# radio.net
KiCad netlist of a schematic drawn in Altium Designer
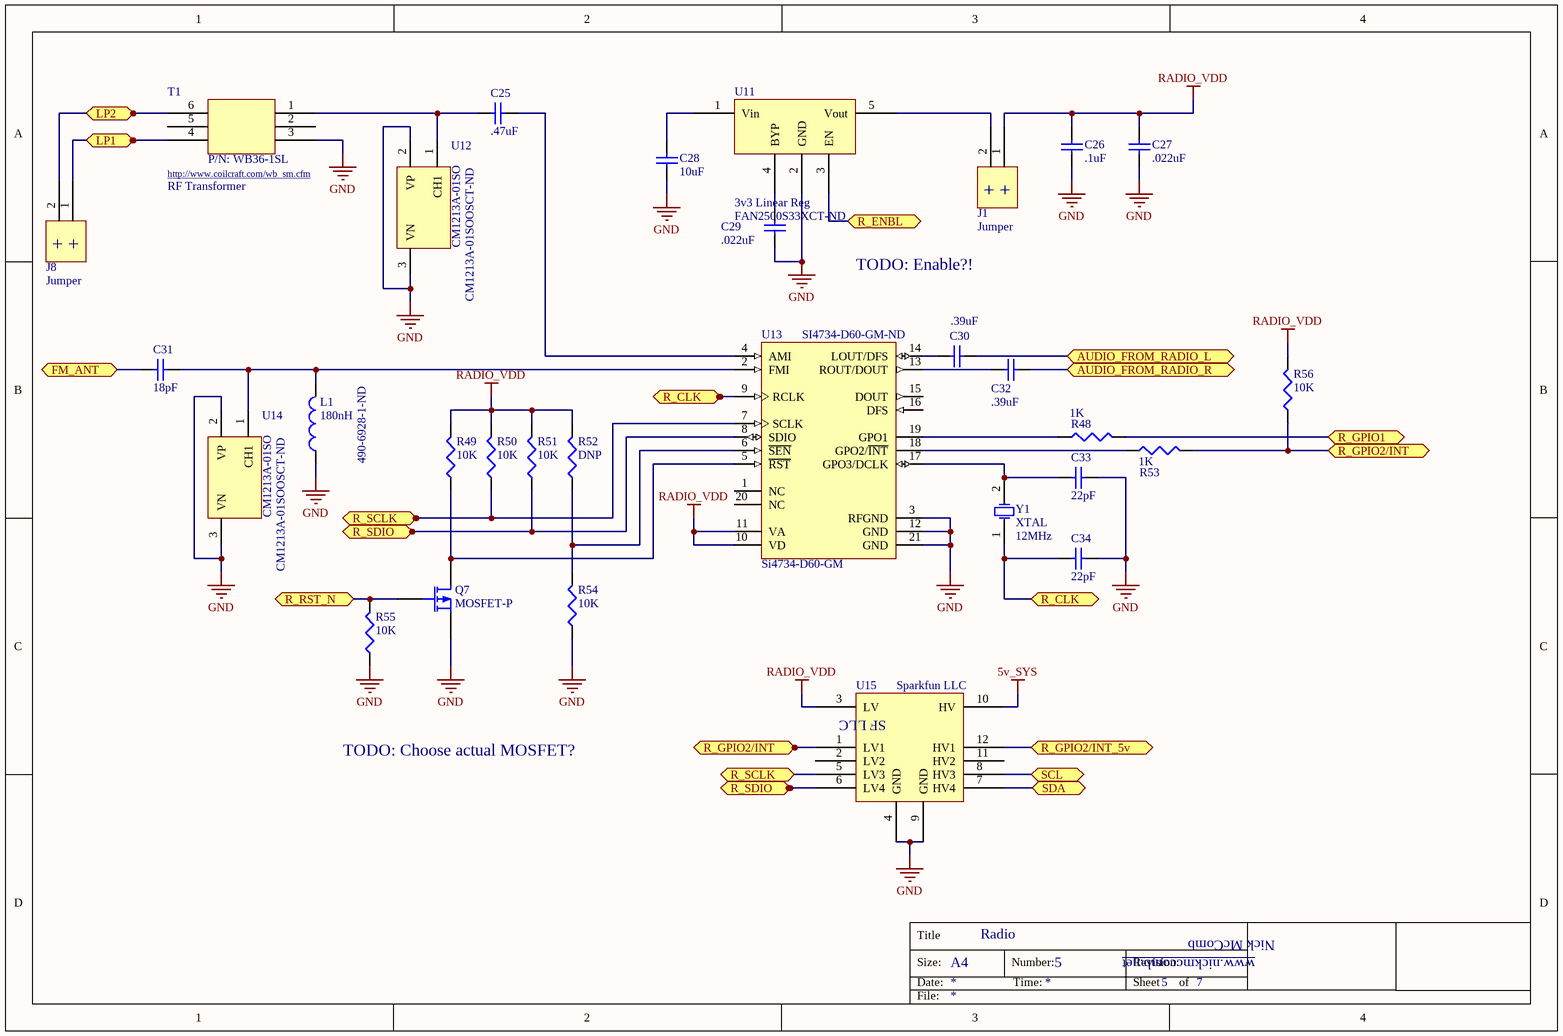
[diagram p0: radio.SchDoc]

(export (version "E")
  (design (tool "Eeschema 10.0.6"))
  (components
    (comp (ref "C25")
      (value ".47uF")
      (footprint "C0805")
      (description "Capacitor")
      (fields (field (name "Comment") "0805 style, by default") (field (name "PUBLISHER") "Altium Limited"))
      (libsource (lib "lab2") (part "Cap"))
    )
    (comp (ref "C26")
      (value ".1uF")
      (footprint "C0805")
      (description "Capacitor")
      (fields (field (name "Comment") "0805 style, by default") (field (name "PUBLISHER") "Altium Limited"))
      (libsource (lib "lab2") (part "Cap"))
    )
    (comp (ref "C27")
      (value ".022uF")
      (footprint "C0805")
      (description "Capacitor")
      (fields (field (name "Comment") "0805 style, by default") (field (name "PUBLISHER") "Altium Limited"))
      (libsource (lib "lab2") (part "Cap"))
    )
    (comp (ref "C28")
      (value "10uF")
      (footprint "C0805")
      (description "Capacitor")
      (fields (field (name "Comment") "0805 style, by default") (field (name "PUBLISHER") "Altium Limited"))
      (libsource (lib "lab2") (part "Cap"))
    )
    (comp (ref "C29")
      (value ".022uF")
      (footprint "C0805")
      (description "Capacitor")
      (fields (field (name "Comment") "0805 style, by default") (field (name "PUBLISHER") "Altium Limited"))
      (libsource (lib "lab2") (part "Cap"))
    )
    (comp (ref "C30")
      (value ".39uF")
      (footprint "C0805")
      (description "Capacitor")
      (fields (field (name "Comment") "0805 style, by default") (field (name "PUBLISHER") "Altium Limited"))
      (libsource (lib "lab2") (part "Cap"))
    )
    (comp (ref "C31")
      (value "18pF")
      (footprint "C0805")
      (description "Capacitor")
      (fields (field (name "Comment") "0805 style, by default") (field (name "PUBLISHER") "Altium Limited"))
      (libsource (lib "lab2") (part "Cap"))
    )
    (comp (ref "C32")
      (value ".39uF")
      (footprint "C0805")
      (description "Capacitor")
      (fields (field (name "Comment") "0805 style, by default") (field (name "PUBLISHER") "Altium Limited"))
      (libsource (lib "lab2") (part "Cap"))
    )
    (comp (ref "C33")
      (value "22pF")
      (footprint "C0805")
      (description "Capacitor")
      (fields (field (name "Comment") "0805 style, by default") (field (name "PUBLISHER") "Altium Limited"))
      (libsource (lib "lab2") (part "Cap"))
    )
    (comp (ref "C34")
      (value "22pF")
      (footprint "C0805")
      (description "Capacitor")
      (fields (field (name "Comment") "0805 style, by default") (field (name "PUBLISHER") "Altium Limited"))
      (libsource (lib "lab2") (part "Cap"))
    )
    (comp (ref "J1") (value "Jumper") (footprint "Jumper") (libsource (lib "lab2") (part "Jumper")))
    (comp (ref "J8") (value "Jumper") (footprint "Jumper") (libsource (lib "lab2") (part "Jumper")))
    (comp (ref "L1")
      (value "180nH")
      (footprint "J1-0603")
      (description "Inductor")
      (fields
        (field (name "SUPPLIER PART NUMBER 1") "490-6928-1-ND")
        (field (name "MANUFACTURER") "Murata")
        (field (name "MANUFACTURER PART NUMBER") "LQW18ANR18J00D")
      )
      (libsource (lib "lab2") (part "Inductor"))
    )
    (comp (ref "Q7")
      (value "MOSFET-P")
      (footprint "E3")
      (description "P-Channel MOSFET")
      (fields (field (name "PUBLISHER") "Altium Limited"))
      (libsource (lib "Miscellaneous Devices") (part "MOSFET-P"))
    )
    (comp (ref "R48")
      (value "1K")
      (footprint "J1-0603")
      (description "Resistor")
      (fields (field (name "PUBLISHER") "Altium Limited"))
      (libsource (lib "lab2") (part "Res3"))
    )
    (comp (ref "R49")
      (value "10K")
      (footprint "J1-0603")
      (description "Resistor")
      (fields (field (name "PUBLISHER") "Altium Limited"))
      (libsource (lib "lab2") (part "Res3"))
    )
    (comp (ref "R50")
      (value "10K")
      (footprint "J1-0603")
      (description "Resistor")
      (fields (field (name "PUBLISHER") "Altium Limited"))
      (libsource (lib "lab2") (part "Res3"))
    )
    (comp (ref "R51")
      (value "10K")
      (footprint "J1-0603")
      (description "Resistor")
      (fields (field (name "PUBLISHER") "Altium Limited"))
      (libsource (lib "lab2") (part "Res3"))
    )
    (comp (ref "R52")
      (value "DNP")
      (footprint "J1-0603")
      (description "Resistor")
      (fields (field (name "PUBLISHER") "Altium Limited"))
      (libsource (lib "lab2") (part "Res3"))
    )
    (comp (ref "R53")
      (value "1K")
      (footprint "J1-0603")
      (description "Resistor")
      (fields (field (name "PUBLISHER") "Altium Limited"))
      (libsource (lib "lab2") (part "Res3"))
    )
    (comp (ref "R54")
      (value "10K")
      (footprint "J1-0603")
      (description "Resistor")
      (fields (field (name "PUBLISHER") "Altium Limited"))
      (libsource (lib "lab2") (part "Res3"))
    )
    (comp (ref "R55")
      (value "10K")
      (footprint "J1-0603")
      (description "Resistor")
      (fields (field (name "PUBLISHER") "Altium Limited"))
      (libsource (lib "lab2") (part "Res3"))
    )
    (comp (ref "R56")
      (value "10K")
      (footprint "J1-0603")
      (description "Resistor")
      (fields (field (name "PUBLISHER") "Altium Limited"))
      (libsource (lib "lab2") (part "Res3"))
    )
    (comp (ref "T1")
      (value "RF Transformer")
      (footprint "WB Series RF Transformers")
      (libsource (lib "lab2") (part "RF Transformer"))
    )
    (comp (ref "U11")
      (value "3v3 Linear Reg")
      (footprint "SOT95P245X110-5N")
      (fields
        (field (name "MANUFACTURER") "Fairchild Semiconductor")
        (field (name "MANUFACTURER PART NUMBER") "FAN2500S33X")
        (field (name "SUPPLIER PART NUMBER 1") "FAN2500S33XCT-ND")
      )
      (libsource (lib "lab2") (part "3v3 Linear Reg"))
    )
    (comp (ref "U12")
      (value "CM1213A-01SO")
      (footprint "ONSC-SOT-23-3-318-08_V")
      (description "1-Channel Low Capacitance ESD Protection Array, 3-Pin SOT-23, Pb-Free, Tape and Reel")
      (fields
        (field (name "MANUFACTURER") "On Semiconductor")
        (field (name "SUPPLIER PART NUMBER 1") "CM1213A-01SOOSCT-ND")
      )
      (libsource (lib "Altium Content Vault") (part "ONSC-CM1213A-SOT-23-3-318-08"))
    )
    (comp (ref "U13")
      (value "Si4734-D60-GM")
      (footprint "SLAB-QFN-20-1700x1700TP_V")
      (description "Broadcast AM / FM / SW / LW Radio Receiver, -20 to 85 degC, 20-pin QFN, Tray")
      (fields
        (field (name "MANUFACTURER") "Silicon Labs")
        (field (name "SUPPLIER PART NUMBER 1") "SI4734-D60-GM-ND")
        (field (name "MANUFACTURER PART NUMBER") "SI4734-D60-GM")
      )
      (libsource (lib "Altium Content Vault") (part "SLAB-Si473X-QFN-20-21"))
    )
    (comp (ref "U14")
      (value "CM1213A-01SO")
      (footprint "ONSC-SOT-23-3-318-08_V")
      (description "1-Channel Low Capacitance ESD Protection Array, 3-Pin SOT-23, Pb-Free, Tape and Reel")
      (fields
        (field (name "MANUFACTURER") "On Semiconductor")
        (field (name "SUPPLIER PART NUMBER 1") "CM1213A-01SOOSCT-ND")
      )
      (libsource (lib "Altium Content Vault") (part "ONSC-CM1213A-SOT-23-3-318-08"))
    )
    (comp (ref "U15")
      (value "Sparkfun LLC")
      (footprint "Sparkfun LLC")
      (libsource (lib "ROSS_PDB") (part "Sparkfun LLC"))
    )
    (comp (ref "Y1")
      (value "XTAL")
      (footprint "XTAL_PDB")
      (description "Crystal Oscillator")
      (fields (field (name "FREQUENCY") "12MHz"))
      (libsource (lib "lab2") (part "XTAL GENERIC"))
    )
  )
  (nets
    (net (code "1") (name "/AUDIO_FROM_RADIO_L") (class "Default")
      (node (ref "C30") (pin "2") (pinfunction "2_2") (pintype "passive"))
    )
    (net (code "2") (name "/AUDIO_FROM_RADIO_R") (class "Default")
      (node (ref "C32") (pin "2") (pinfunction "2_2") (pintype "passive"))
    )
    (net (code "3") (name "/FM_ANT") (class "Default")
      (node (ref "C31") (pin "2") (pinfunction "2_2") (pintype "passive"))
    )
    (net (code "4") (name "/LP1") (class "Default")
      (node (ref "J8") (pin "1") (pintype "passive"))
      (node (ref "T1") (pin "4") (pintype "passive"))
    )
    (net (code "5") (name "/LP2") (class "Default")
      (node (ref "J8") (pin "2") (pintype "passive"))
      (node (ref "T1") (pin "6") (pintype "passive"))
    )
    (net (code "6") (name "/R_CLK") (class "Default")
      (node (ref "C34") (pin "2") (pinfunction "2_2") (pintype "passive"))
      (node (ref "U13") (pin "9") (pinfunction "RCLK_9") (pintype "input"))
      (node (ref "Y1") (pin "1") (pinfunction "OSC1_1") (pintype "passive"))
    )
    (net (code "7") (name "/R_ENBL") (class "Default")
      (node (ref "U11") (pin "3") (pinfunction "EN_3") (pintype "passive"))
    )
    (net (code "8") (name "/R_GPIO1") (class "Default")
      (node (ref "R48") (pin "2") (pinfunction "2_2") (pintype "passive"))
    )
    (net (code "9") (name "/R_GPIO2{slash}INT") (class "Default")
      (node (ref "R53") (pin "2") (pinfunction "2_2") (pintype "passive"))
      (node (ref "R56") (pin "1") (pinfunction "1_1") (pintype "passive"))
      (node (ref "U15") (pin "1") (pinfunction "LV1_1") (pintype "passive"))
    )
    (net (code "10") (name "/R_GPIO2{slash}INT_5v") (class "Default")
      (node (ref "U15") (pin "12") (pinfunction "HV1_12") (pintype "passive"))
    )
    (net (code "11") (name "/R_RST_N") (class "Default")
      (node (ref "Q7") (pin "2") (pinfunction "G_2") (pintype "passive"))
      (node (ref "R55") (pin "2") (pinfunction "2_2") (pintype "passive"))
    )
    (net (code "12") (name "/R_SCLK") (class "Default")
      (node (ref "R50") (pin "1") (pinfunction "1_1") (pintype "passive"))
      (node (ref "U13") (pin "7") (pinfunction "SCLK_7") (pintype "input"))
      (node (ref "U15") (pin "5") (pinfunction "LV3_5") (pintype "passive"))
    )
    (net (code "13") (name "/R_SDIO") (class "Default")
      (node (ref "R51") (pin "1") (pinfunction "1_1") (pintype "passive"))
      (node (ref "U13") (pin "8") (pinfunction "SDIO_8") (pintype "bidirectional"))
      (node (ref "U15") (pin "6") (pinfunction "LV4_6") (pintype "passive"))
    )
    (net (code "14") (name "/SCL") (class "Default")
      (node (ref "U15") (pin "8") (pinfunction "HV3_8") (pintype "passive"))
    )
    (net (code "15") (name "/SDA") (class "Default")
      (node (ref "U15") (pin "7") (pinfunction "HV4_7") (pintype "passive"))
    )
    (net (code "16") (name "5v_SYS") (class "Default")
      (node (ref "U15") (pin "10") (pinfunction "HV_10") (pintype "passive"))
    )
    (net (code "17") (name "GND") (class "Default")
      (node (ref "C26") (pin "1") (pinfunction "1_1") (pintype "passive"))
      (node (ref "C27") (pin "1") (pinfunction "1_1") (pintype "passive"))
      (node (ref "C28") (pin "1") (pinfunction "1_1") (pintype "passive"))
      (node (ref "C29") (pin "1") (pinfunction "1_1") (pintype "passive"))
      (node (ref "C33") (pin "1") (pinfunction "1_1") (pintype "passive"))
      (node (ref "C34") (pin "1") (pinfunction "1_1") (pintype "passive"))
      (node (ref "L1") (pin "1") (pinfunction "1_1") (pintype "passive"))
      (node (ref "Q7") (pin "3") (pinfunction "S_3") (pintype "passive"))
      (node (ref "R54") (pin "1") (pinfunction "1_1") (pintype "passive"))
      (node (ref "R55") (pin "1") (pinfunction "1_1") (pintype "passive"))
      (node (ref "T1") (pin "3") (pintype "passive"))
      (node (ref "U11") (pin "2") (pinfunction "GND_2") (pintype "passive"))
      (node (ref "U12") (pin "2") (pinfunction "VP_2") (pintype "power_in"))
      (node (ref "U12") (pin "3") (pinfunction "VN_3") (pintype "power_in"))
      (node (ref "U13") (pin "12") (pinfunction "GND_12") (pintype "power_in"))
      (node (ref "U13") (pin "21") (pinfunction "GND_21") (pintype "power_in"))
      (node (ref "U13") (pin "3") (pinfunction "RFGND_3") (pintype "power_in"))
      (node (ref "U14") (pin "2") (pinfunction "VP_2") (pintype "power_in"))
      (node (ref "U14") (pin "3") (pinfunction "VN_3") (pintype "power_in"))
      (node (ref "U15") (pin "4") (pinfunction "GND_4") (pintype "passive"))
      (node (ref "U15") (pin "9") (pinfunction "GND_9") (pintype "passive"))
    )
    (net (code "18") (name "Net-(Q7-D)") (class "Default")
      (node (ref "Q7") (pin "1") (pinfunction "D_1") (pintype "passive"))
      (node (ref "R49") (pin "1") (pinfunction "1_1") (pintype "passive"))
      (node (ref "U13") (pin "5") (pinfunction "~{RST}_5") (pintype "input"))
    )
    (net (code "19") (name "Net-(U11-BYP)") (class "Default")
      (node (ref "C29") (pin "2") (pinfunction "2_2") (pintype "passive"))
      (node (ref "U11") (pin "4") (pinfunction "BYP_4") (pintype "passive"))
    )
    (net (code "20") (name "Net-(U11-Vin)") (class "Default")
      (node (ref "C28") (pin "2") (pinfunction "2_2") (pintype "passive"))
      (node (ref "U11") (pin "1") (pinfunction "Vin_1") (pintype "passive"))
    )
    (net (code "21") (name "Net-(U11-Vout)") (class "Default")
      (node (ref "J1") (pin "2") (pintype "passive"))
      (node (ref "U11") (pin "5") (pinfunction "Vout_5") (pintype "passive"))
    )
    (net (code "22") (name "Net-(U12-CH1)") (class "Default")
      (node (ref "C25") (pin "2") (pinfunction "2_2") (pintype "passive"))
      (node (ref "T1") (pin "1") (pintype "passive"))
      (node (ref "U12") (pin "1") (pinfunction "CH1_1") (pintype "passive"))
    )
    (net (code "23") (name "Net-(U13-AMI)") (class "Default")
      (node (ref "C25") (pin "1") (pinfunction "1_1") (pintype "passive"))
      (node (ref "U13") (pin "4") (pinfunction "AMI_4") (pintype "input"))
    )
    (net (code "24") (name "Net-(U13-FMI)") (class "Default")
      (node (ref "C31") (pin "1") (pinfunction "1_1") (pintype "passive"))
      (node (ref "L1") (pin "2") (pinfunction "2_2") (pintype "passive"))
      (node (ref "U13") (pin "2") (pinfunction "FMI_2") (pintype "input"))
      (node (ref "U14") (pin "1") (pinfunction "CH1_1") (pintype "passive"))
    )
    (net (code "25") (name "Net-(U13-GPO1)") (class "Default")
      (node (ref "R48") (pin "1") (pinfunction "1_1") (pintype "passive"))
      (node (ref "U13") (pin "19") (pinfunction "GPO1_19") (pintype "tri_state"))
    )
    (net (code "26") (name "Net-(U13-GPO2{slash}~{INT})") (class "Default")
      (node (ref "R53") (pin "1") (pinfunction "1_1") (pintype "passive"))
      (node (ref "U13") (pin "18") (pinfunction "GPO2/~{INT}_18") (pintype "tri_state"))
    )
    (net (code "27") (name "Net-(U13-GPO3{slash}DCLK)") (class "Default")
      (node (ref "C33") (pin "2") (pinfunction "2_2") (pintype "passive"))
      (node (ref "U13") (pin "17") (pinfunction "GPO3/DCLK_17") (pintype "bidirectional"))
      (node (ref "Y1") (pin "2") (pinfunction "OSC2_2") (pintype "passive"))
    )
    (net (code "28") (name "Net-(U13-LOUT{slash}DFS)") (class "Default")
      (node (ref "C30") (pin "1") (pinfunction "1_1") (pintype "passive"))
      (node (ref "U13") (pin "14") (pinfunction "LOUT/DFS_14") (pintype "bidirectional"))
    )
    (net (code "29") (name "Net-(U13-ROUT{slash}DOUT)") (class "Default")
      (node (ref "C32") (pin "1") (pinfunction "1_1") (pintype "passive"))
      (node (ref "U13") (pin "13") (pinfunction "ROUT/DOUT_13") (pintype "output"))
    )
    (net (code "30") (name "Net-(U13-~{SEN})") (class "Default")
      (node (ref "R52") (pin "1") (pinfunction "1_1") (pintype "passive"))
      (node (ref "R54") (pin "2") (pinfunction "2_2") (pintype "passive"))
      (node (ref "U13") (pin "6") (pinfunction "~{SEN}_6") (pintype "input"))
    )
    (net (code "31") (name "RADIO_VDD") (class "Default")
      (node (ref "C26") (pin "2") (pinfunction "2_2") (pintype "passive"))
      (node (ref "C27") (pin "2") (pinfunction "2_2") (pintype "passive"))
      (node (ref "J1") (pin "1") (pintype "passive"))
      (node (ref "R49") (pin "2") (pinfunction "2_2") (pintype "passive"))
      (node (ref "R50") (pin "2") (pinfunction "2_2") (pintype "passive"))
      (node (ref "R51") (pin "2") (pinfunction "2_2") (pintype "passive"))
      (node (ref "R52") (pin "2") (pinfunction "2_2") (pintype "passive"))
      (node (ref "R56") (pin "2") (pinfunction "2_2") (pintype "passive"))
      (node (ref "U13") (pin "10") (pinfunction "VD_10") (pintype "power_in"))
      (node (ref "U13") (pin "11") (pinfunction "VA_11") (pintype "power_in"))
      (node (ref "U15") (pin "3") (pinfunction "LV_3") (pintype "passive"))
    )
    (net (code "32") (name "unconnected-(T1-Pad2)") (class "Default")
      (node (ref "T1") (pin "2") (pintype "passive"))
    )
    (net (code "33") (name "unconnected-(T1-Pad5)") (class "Default")
      (node (ref "T1") (pin "5") (pintype "passive"))
    )
    (net (code "34") (name "unconnected-(U13-DFS-Pad16)") (class "Default")
      (node (ref "U13") (pin "16") (pinfunction "DFS_16") (pintype "input"))
    )
    (net (code "35") (name "unconnected-(U13-DOUT-Pad15)") (class "Default")
      (node (ref "U13") (pin "15") (pinfunction "DOUT_15") (pintype "output"))
    )
    (net (code "36") (name "unconnected-(U13-NC-Pad1)") (class "Default")
      (node (ref "U13") (pin "1") (pinfunction "NC_1") (pintype "passive"))
    )
    (net (code "37") (name "unconnected-(U13-NC-Pad20)") (class "Default")
      (node (ref "U13") (pin "20") (pinfunction "NC_20") (pintype "passive"))
    )
    (net (code "38") (name "unconnected-(U15-HV2-Pad11)") (class "Default")
      (node (ref "U15") (pin "11") (pinfunction "HV2_11") (pintype "passive"))
    )
    (net (code "39") (name "unconnected-(U15-LV2-Pad2)") (class "Default")
      (node (ref "U15") (pin "2") (pinfunction "LV2_2") (pintype "passive"))
    )
  )
)
